# Sheet.net
KiCad netlist of a schematic drawn in Altium Designer
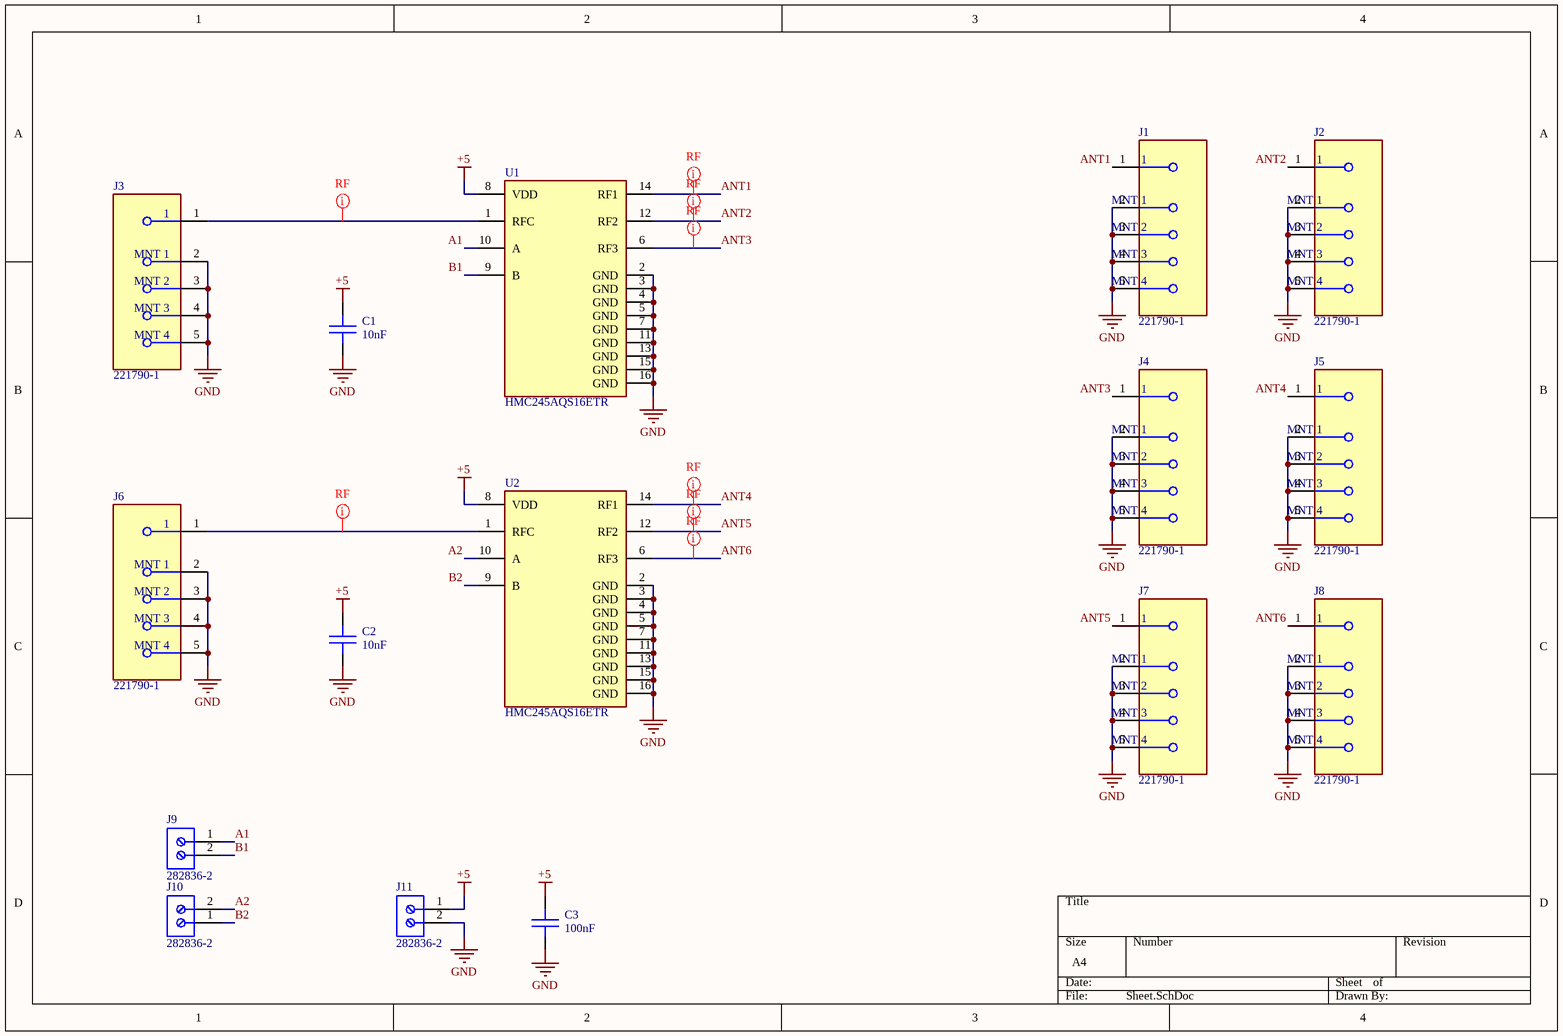
[diagram p0: Sheet.SchDoc]

(export (version "E")
  (design (tool "Eeschema 10.0.6"))
  (components
    (comp (ref "C1")
      (value "10nF")
      (footprint "C0603 (1608)")
      (fields (field (name "Comment") "Cap SMD"))
      (libsource (lib "Moto Symbol Lib") (part "Cap SMD"))
    )
    (comp (ref "C2")
      (value "10nF")
      (footprint "C0603 (1608)")
      (fields (field (name "Comment") "Cap SMD"))
      (libsource (lib "Moto Symbol Lib") (part "Cap SMD"))
    )
    (comp (ref "C3")
      (value "100nF")
      (footprint "C0603 (1608)")
      (fields (field (name "Comment") "Cap SMD"))
      (libsource (lib "Moto Symbol Lib") (part "Cap SMD"))
    )
    (comp (ref "J1")
      (value "221790-1")
      (footprint "FP-221790-1-MFG")
      (description "CONN SMA JACK R/A 50 OHM PCB")
      (fields
        (field (name "OCTOPART") "https://octopart.com/2217901-te+connectivity+%2F+amp-3339836")
        (field (name "MANUFACTURER") "TE Connectivity / AMP")
      )
      (libsource (lib "Altium Content Vault") (part "c65b8a639cdaef1819ea20b5466f8fa"))
    )
    (comp (ref "J2")
      (value "221790-1")
      (footprint "FP-221790-1-MFG")
      (description "CONN SMA JACK R/A 50 OHM PCB")
      (fields
        (field (name "OCTOPART") "https://octopart.com/2217901-te+connectivity+%2F+amp-3339836")
        (field (name "MANUFACTURER") "TE Connectivity / AMP")
      )
      (libsource (lib "Altium Content Vault") (part "c65b8a639cdaef1819ea20b5466f8fa"))
    )
    (comp (ref "J3")
      (value "221790-1")
      (footprint "FP-221790-1-MFG")
      (description "CONN SMA JACK R/A 50 OHM PCB")
      (fields
        (field (name "OCTOPART") "https://octopart.com/2217901-te+connectivity+%2F+amp-3339836")
        (field (name "MANUFACTURER") "TE Connectivity / AMP")
      )
      (libsource (lib "") (part "c65b8a639cdaef1819ea20b5466f8fa_1"))
    )
    (comp (ref "J4")
      (value "221790-1")
      (footprint "FP-221790-1-MFG")
      (description "CONN SMA JACK R/A 50 OHM PCB")
      (fields
        (field (name "OCTOPART") "https://octopart.com/2217901-te+connectivity+%2F+amp-3339836")
        (field (name "MANUFACTURER") "TE Connectivity / AMP")
      )
      (libsource (lib "Altium Content Vault") (part "c65b8a639cdaef1819ea20b5466f8fa"))
    )
    (comp (ref "J5")
      (value "221790-1")
      (footprint "FP-221790-1-MFG")
      (description "CONN SMA JACK R/A 50 OHM PCB")
      (fields
        (field (name "OCTOPART") "https://octopart.com/2217901-te+connectivity+%2F+amp-3339836")
        (field (name "MANUFACTURER") "TE Connectivity / AMP")
      )
      (libsource (lib "Altium Content Vault") (part "c65b8a639cdaef1819ea20b5466f8fa"))
    )
    (comp (ref "J6")
      (value "221790-1")
      (footprint "FP-221790-1-MFG")
      (description "CONN SMA JACK R/A 50 OHM PCB")
      (fields
        (field (name "OCTOPART") "https://octopart.com/2217901-te+connectivity+%2F+amp-3339836")
        (field (name "MANUFACTURER") "TE Connectivity / AMP")
      )
      (libsource (lib "") (part "c65b8a639cdaef1819ea20b5466f8fa_1"))
    )
    (comp (ref "J7")
      (value "221790-1")
      (footprint "FP-221790-1-MFG")
      (description "CONN SMA JACK R/A 50 OHM PCB")
      (fields
        (field (name "OCTOPART") "https://octopart.com/2217901-te+connectivity+%2F+amp-3339836")
        (field (name "MANUFACTURER") "TE Connectivity / AMP")
      )
      (libsource (lib "Altium Content Vault") (part "c65b8a639cdaef1819ea20b5466f8fa"))
    )
    (comp (ref "J8")
      (value "221790-1")
      (footprint "FP-221790-1-MFG")
      (description "CONN SMA JACK R/A 50 OHM PCB")
      (fields
        (field (name "OCTOPART") "https://octopart.com/2217901-te+connectivity+%2F+amp-3339836")
        (field (name "MANUFACTURER") "TE Connectivity / AMP")
      )
      (libsource (lib "Altium Content Vault") (part "c65b8a639cdaef1819ea20b5466f8fa"))
    )
    (comp (ref "J9")
      (value "282836-2")
      (footprint "TECO-282836-2_V")
      (description "Female Header, Pitch 5 mm, 1 x 2 Position, Height 10 mm, Tail Length 3.5 mm, Rohs, Bulk")
      (fields (field (name "VOLTAGE") "300V") (field (name "MANUFACTURER") "TE Connectivity"))
      (libsource (lib "Altium Content Vault") (part "CN-1P-F-TB2"))
    )
    (comp (ref "J10")
      (value "282836-2")
      (footprint "TECO-282836-2_V")
      (description "Female Header, Pitch 5 mm, 1 x 2 Position, Height 10 mm, Tail Length 3.5 mm, Rohs, Bulk")
      (fields (field (name "VOLTAGE") "300V") (field (name "MANUFACTURER") "TE Connectivity"))
      (libsource (lib "Altium Content Vault") (part "CN-1P-F-TB2"))
    )
    (comp (ref "J11")
      (value "282836-2")
      (footprint "TECO-282836-2_V")
      (description "Female Header, Pitch 5 mm, 1 x 2 Position, Height 10 mm, Tail Length 3.5 mm, Rohs, Bulk")
      (fields (field (name "VOLTAGE") "300V") (field (name "MANUFACTURER") "TE Connectivity"))
      (libsource (lib "Altium Content Vault") (part "CN-1P-F-TB2"))
    )
    (comp (ref "U1")
      (value "HMC245AQS16ETR")
      (footprint "FP-RQ-16-IPC_C")
      (description "IC RF SWITCH SP3T 3.5GHZ 16QSOP")
      (libsource (lib "Altium Content Vault") (part "30309a12785310b9221685bf002e779"))
    )
    (comp (ref "U2")
      (value "HMC245AQS16ETR")
      (footprint "FP-RQ-16-IPC_C")
      (description "IC RF SWITCH SP3T 3.5GHZ 16QSOP")
      (libsource (lib "Altium Content Vault") (part "30309a12785310b9221685bf002e779"))
    )
  )
  (nets
    (net (code "1") (name "+5") (class "Default")
      (node (ref "C1") (pin "2") (pinfunction "2_2") (pintype "power_in"))
      (node (ref "C2") (pin "2") (pinfunction "2_2") (pintype "power_in"))
      (node (ref "C3") (pin "2") (pinfunction "2_2") (pintype "power_in"))
      (node (ref "J11") (pin "1") (pinfunction "1_1") (pintype "passive"))
      (node (ref "U1") (pin "8") (pinfunction "VDD_8") (pintype "power_in"))
      (node (ref "U2") (pin "8") (pinfunction "VDD_8") (pintype "power_in"))
    )
    (net (code "2") (name "/A1") (class "Default")
      (node (ref "J9") (pin "1") (pinfunction "1_1") (pintype "passive"))
      (node (ref "U1") (pin "10") (pinfunction "A_10") (pintype "passive"))
    )
    (net (code "3") (name "/A2") (class "Default")
      (node (ref "J10") (pin "2") (pinfunction "2_2") (pintype "passive"))
      (node (ref "U2") (pin "10") (pinfunction "A_10") (pintype "passive"))
    )
    (net (code "4") (name "/ANT1") (class "Default")
      (node (ref "J1") (pin "1") (pinfunction "1_1") (pintype "passive"))
      (node (ref "U1") (pin "14") (pinfunction "RF1_14") (pintype "passive"))
    )
    (net (code "5") (name "/ANT2") (class "Default")
      (node (ref "J2") (pin "1") (pinfunction "1_1") (pintype "passive"))
      (node (ref "U1") (pin "12") (pinfunction "RF2_12") (pintype "passive"))
    )
    (net (code "6") (name "/ANT3") (class "Default")
      (node (ref "J4") (pin "1") (pinfunction "1_1") (pintype "passive"))
      (node (ref "U1") (pin "6") (pinfunction "RF3_6") (pintype "passive"))
    )
    (net (code "7") (name "/ANT4") (class "Default")
      (node (ref "J5") (pin "1") (pinfunction "1_1") (pintype "passive"))
      (node (ref "U2") (pin "14") (pinfunction "RF1_14") (pintype "passive"))
    )
    (net (code "8") (name "/ANT5") (class "Default")
      (node (ref "J7") (pin "1") (pinfunction "1_1") (pintype "passive"))
      (node (ref "U2") (pin "12") (pinfunction "RF2_12") (pintype "passive"))
    )
    (net (code "9") (name "/ANT6") (class "Default")
      (node (ref "J8") (pin "1") (pinfunction "1_1") (pintype "passive"))
      (node (ref "U2") (pin "6") (pinfunction "RF3_6") (pintype "passive"))
    )
    (net (code "10") (name "/B1") (class "Default")
      (node (ref "J9") (pin "2") (pinfunction "2_2") (pintype "passive"))
      (node (ref "U1") (pin "9") (pinfunction "B_9") (pintype "passive"))
    )
    (net (code "11") (name "/B2") (class "Default")
      (node (ref "J10") (pin "1") (pinfunction "1_1") (pintype "passive"))
      (node (ref "U2") (pin "9") (pinfunction "B_9") (pintype "passive"))
    )
    (net (code "12") (name "GND") (class "Default")
      (node (ref "C1") (pin "1") (pinfunction "1_1") (pintype "power_in"))
      (node (ref "C2") (pin "1") (pinfunction "1_1") (pintype "power_in"))
      (node (ref "C3") (pin "1") (pinfunction "1_1") (pintype "power_in"))
      (node (ref "J1") (pin "2") (pinfunction "MNT_1_2") (pintype "passive"))
      (node (ref "J1") (pin "3") (pinfunction "MNT_2_3") (pintype "passive"))
      (node (ref "J1") (pin "4") (pinfunction "MNT_3_4") (pintype "passive"))
      (node (ref "J1") (pin "5") (pinfunction "MNT_4_5") (pintype "passive"))
      (node (ref "J11") (pin "2") (pinfunction "2_2") (pintype "passive"))
      (node (ref "J2") (pin "2") (pinfunction "MNT_1_2") (pintype "passive"))
      (node (ref "J2") (pin "3") (pinfunction "MNT_2_3") (pintype "passive"))
      (node (ref "J2") (pin "4") (pinfunction "MNT_3_4") (pintype "passive"))
      (node (ref "J2") (pin "5") (pinfunction "MNT_4_5") (pintype "passive"))
      (node (ref "J3") (pin "2") (pinfunction "MNT_1_2") (pintype "passive"))
      (node (ref "J3") (pin "3") (pinfunction "MNT_2_3") (pintype "passive"))
      (node (ref "J3") (pin "4") (pinfunction "MNT_3_4") (pintype "passive"))
      (node (ref "J3") (pin "5") (pinfunction "MNT_4_5") (pintype "passive"))
      (node (ref "J4") (pin "2") (pinfunction "MNT_1_2") (pintype "passive"))
      (node (ref "J4") (pin "3") (pinfunction "MNT_2_3") (pintype "passive"))
      (node (ref "J4") (pin "4") (pinfunction "MNT_3_4") (pintype "passive"))
      (node (ref "J4") (pin "5") (pinfunction "MNT_4_5") (pintype "passive"))
      (node (ref "J5") (pin "2") (pinfunction "MNT_1_2") (pintype "passive"))
      (node (ref "J5") (pin "3") (pinfunction "MNT_2_3") (pintype "passive"))
      (node (ref "J5") (pin "4") (pinfunction "MNT_3_4") (pintype "passive"))
      (node (ref "J5") (pin "5") (pinfunction "MNT_4_5") (pintype "passive"))
      (node (ref "J6") (pin "2") (pinfunction "MNT_1_2") (pintype "passive"))
      (node (ref "J6") (pin "3") (pinfunction "MNT_2_3") (pintype "passive"))
      (node (ref "J6") (pin "4") (pinfunction "MNT_3_4") (pintype "passive"))
      (node (ref "J6") (pin "5") (pinfunction "MNT_4_5") (pintype "passive"))
      (node (ref "J7") (pin "2") (pinfunction "MNT_1_2") (pintype "passive"))
      (node (ref "J7") (pin "3") (pinfunction "MNT_2_3") (pintype "passive"))
      (node (ref "J7") (pin "4") (pinfunction "MNT_3_4") (pintype "passive"))
      (node (ref "J7") (pin "5") (pinfunction "MNT_4_5") (pintype "passive"))
      (node (ref "J8") (pin "2") (pinfunction "MNT_1_2") (pintype "passive"))
      (node (ref "J8") (pin "3") (pinfunction "MNT_2_3") (pintype "passive"))
      (node (ref "J8") (pin "4") (pinfunction "MNT_3_4") (pintype "passive"))
      (node (ref "J8") (pin "5") (pinfunction "MNT_4_5") (pintype "passive"))
      (node (ref "U1") (pin "11") (pinfunction "GND_11") (pintype "power_in"))
      (node (ref "U1") (pin "13") (pinfunction "GND_13") (pintype "power_in"))
      (node (ref "U1") (pin "15") (pinfunction "GND_15") (pintype "power_in"))
      (node (ref "U1") (pin "16") (pinfunction "GND_16") (pintype "power_in"))
      (node (ref "U1") (pin "2") (pinfunction "GND_2") (pintype "power_in"))
      (node (ref "U1") (pin "3") (pinfunction "GND_3") (pintype "power_in"))
      (node (ref "U1") (pin "4") (pinfunction "GND_4") (pintype "power_in"))
      (node (ref "U1") (pin "5") (pinfunction "GND_5") (pintype "power_in"))
      (node (ref "U1") (pin "7") (pinfunction "GND_7") (pintype "power_in"))
      (node (ref "U2") (pin "11") (pinfunction "GND_11") (pintype "power_in"))
      (node (ref "U2") (pin "13") (pinfunction "GND_13") (pintype "power_in"))
      (node (ref "U2") (pin "15") (pinfunction "GND_15") (pintype "power_in"))
      (node (ref "U2") (pin "16") (pinfunction "GND_16") (pintype "power_in"))
      (node (ref "U2") (pin "2") (pinfunction "GND_2") (pintype "power_in"))
      (node (ref "U2") (pin "3") (pinfunction "GND_3") (pintype "power_in"))
      (node (ref "U2") (pin "4") (pinfunction "GND_4") (pintype "power_in"))
      (node (ref "U2") (pin "5") (pinfunction "GND_5") (pintype "power_in"))
      (node (ref "U2") (pin "7") (pinfunction "GND_7") (pintype "power_in"))
    )
    (net (code "13") (name "Net-(U1-RFC)") (class "Default")
      (node (ref "J3") (pin "1") (pinfunction "1_1") (pintype "passive"))
      (node (ref "U1") (pin "1") (pinfunction "RFC_1") (pintype "passive"))
    )
    (net (code "14") (name "Net-(U2-RFC)") (class "Default")
      (node (ref "J6") (pin "1") (pinfunction "1_1") (pintype "passive"))
      (node (ref "U2") (pin "1") (pinfunction "RFC_1") (pintype "passive"))
    )
  )
)
